# sensor.net
KiCad netlist of a schematic drawn in EAGLE
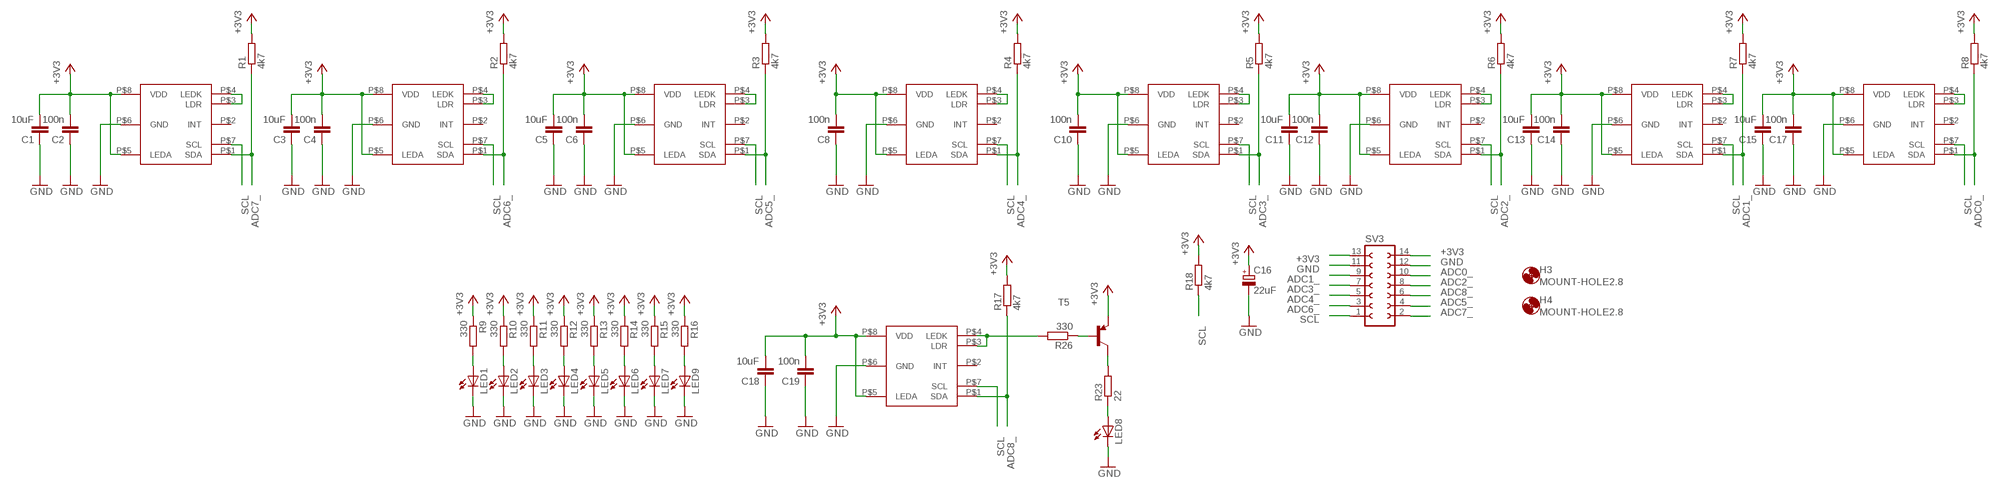
[diagram p0: schematic, sheet 1]

(export (version "E")
  (design (tool "Eeschema 10.0.6"))
  (components
    (comp (ref "C1")
      (value "10uF")
      (footprint "eagle-import:C0805")
      (libsource (lib "eagle-import") (part "C-EUC0805"))
    )
    (comp (ref "C2")
      (value "100n")
      (footprint "eagle-import:C0805")
      (libsource (lib "eagle-import") (part "C-EUC0805"))
    )
    (comp (ref "C3")
      (value "10uF")
      (footprint "eagle-import:C0805")
      (libsource (lib "eagle-import") (part "C-EUC0805"))
    )
    (comp (ref "C4")
      (value "100n")
      (footprint "eagle-import:C0805")
      (libsource (lib "eagle-import") (part "C-EUC0805"))
    )
    (comp (ref "C5")
      (value "10uF")
      (footprint "eagle-import:C0805")
      (libsource (lib "eagle-import") (part "C-EUC0805"))
    )
    (comp (ref "C6")
      (value "100n")
      (footprint "eagle-import:C0805")
      (libsource (lib "eagle-import") (part "C-EUC0805"))
    )
    (comp (ref "C8")
      (value "100n")
      (footprint "eagle-import:C0805")
      (libsource (lib "eagle-import") (part "C-EUC0805"))
    )
    (comp (ref "C10")
      (value "100n")
      (footprint "eagle-import:C0805")
      (libsource (lib "eagle-import") (part "C-EUC0805"))
    )
    (comp (ref "C11")
      (value "10uF")
      (footprint "eagle-import:C0805")
      (libsource (lib "eagle-import") (part "C-EUC0805"))
    )
    (comp (ref "C12")
      (value "100n")
      (footprint "eagle-import:C0805")
      (libsource (lib "eagle-import") (part "C-EUC0805"))
    )
    (comp (ref "C13")
      (value "10uF")
      (footprint "eagle-import:C0805")
      (libsource (lib "eagle-import") (part "C-EUC0805"))
    )
    (comp (ref "C14")
      (value "100n")
      (footprint "eagle-import:C0805")
      (libsource (lib "eagle-import") (part "C-EUC0805"))
    )
    (comp (ref "C15")
      (value "10uF")
      (footprint "eagle-import:C0805")
      (libsource (lib "eagle-import") (part "C-EUC0805"))
    )
    (comp (ref "C16")
      (value "22uF")
      (footprint "eagle-import:153CLV-0505")
      (libsource (lib "eagle-import") (part "CPOL-EU153CLV-0505"))
    )
    (comp (ref "C17")
      (value "100n")
      (footprint "eagle-import:C0805")
      (libsource (lib "eagle-import") (part "C-EUC0805"))
    )
    (comp (ref "C18")
      (value "10uF")
      (footprint "eagle-import:C0805")
      (libsource (lib "eagle-import") (part "C-EUC0805"))
    )
    (comp (ref "C19")
      (value "100n")
      (footprint "eagle-import:C0805")
      (libsource (lib "eagle-import") (part "C-EUC0805"))
    )
    (comp (ref "H3")
      (value "MOUNT-HOLE2.8")
      (footprint "eagle-import:2,8")
      (libsource (lib "eagle-import") (part "MOUNT-HOLE2.8"))
    )
    (comp (ref "H4")
      (value "MOUNT-HOLE2.8")
      (footprint "eagle-import:2,8")
      (libsource (lib "eagle-import") (part "MOUNT-HOLE2.8"))
    )
    (comp (ref "LED1")
      (value "LEDCHIPLED_1206")
      (footprint "eagle-import:CHIPLED_1206")
      (libsource (lib "eagle-import") (part "my_parts_LEDCHIPLED_1206"))
    )
    (comp (ref "LED2")
      (value "LEDCHIPLED_1206")
      (footprint "eagle-import:CHIPLED_1206")
      (libsource (lib "eagle-import") (part "my_parts_LEDCHIPLED_1206"))
    )
    (comp (ref "LED3")
      (value "LEDCHIPLED_1206")
      (footprint "eagle-import:CHIPLED_1206")
      (libsource (lib "eagle-import") (part "my_parts_LEDCHIPLED_1206"))
    )
    (comp (ref "LED4")
      (value "LEDCHIPLED_1206")
      (footprint "eagle-import:CHIPLED_1206")
      (libsource (lib "eagle-import") (part "my_parts_LEDCHIPLED_1206"))
    )
    (comp (ref "LED5")
      (value "LEDCHIPLED_1206")
      (footprint "eagle-import:CHIPLED_1206")
      (libsource (lib "eagle-import") (part "my_parts_LEDCHIPLED_1206"))
    )
    (comp (ref "LED6")
      (value "LEDCHIPLED_1206")
      (footprint "eagle-import:CHIPLED_1206")
      (libsource (lib "eagle-import") (part "my_parts_LEDCHIPLED_1206"))
    )
    (comp (ref "LED7")
      (value "LEDCHIPLED_1206")
      (footprint "eagle-import:CHIPLED_1206")
      (libsource (lib "eagle-import") (part "my_parts_LEDCHIPLED_1206"))
    )
    (comp (ref "LED8")
      (value "LED5MM")
      (footprint "eagle-import:LED5MM")
      (libsource (lib "eagle-import") (part "LED5MM"))
    )
    (comp (ref "LED9")
      (value "LEDCHIPLED_1206")
      (footprint "eagle-import:CHIPLED_1206")
      (libsource (lib "eagle-import") (part "my_parts_LEDCHIPLED_1206"))
    )
    (comp (ref "R1")
      (value "4k7")
      (footprint "eagle-import:M0805")
      (libsource (lib "eagle-import") (part "R-EU_M0805"))
    )
    (comp (ref "R2")
      (value "4k7")
      (footprint "eagle-import:M0805")
      (libsource (lib "eagle-import") (part "R-EU_M0805"))
    )
    (comp (ref "R3")
      (value "4k7")
      (footprint "eagle-import:M0805")
      (libsource (lib "eagle-import") (part "R-EU_M0805"))
    )
    (comp (ref "R4")
      (value "4k7")
      (footprint "eagle-import:M0805")
      (libsource (lib "eagle-import") (part "R-EU_M0805"))
    )
    (comp (ref "R5")
      (value "4k7")
      (footprint "eagle-import:M0805")
      (libsource (lib "eagle-import") (part "R-EU_M0805"))
    )
    (comp (ref "R6")
      (value "4k7")
      (footprint "eagle-import:M0805")
      (libsource (lib "eagle-import") (part "R-EU_M0805"))
    )
    (comp (ref "R7")
      (value "4k7")
      (footprint "eagle-import:M0805")
      (libsource (lib "eagle-import") (part "R-EU_M0805"))
    )
    (comp (ref "R8")
      (value "4k7")
      (footprint "eagle-import:M0805")
      (libsource (lib "eagle-import") (part "R-EU_M0805"))
    )
    (comp (ref "R9")
      (value "330")
      (footprint "eagle-import:M0805")
      (libsource (lib "eagle-import") (part "R-EU_M0805"))
    )
    (comp (ref "R10")
      (value "330")
      (footprint "eagle-import:M0805")
      (libsource (lib "eagle-import") (part "R-EU_M0805"))
    )
    (comp (ref "R11")
      (value "330")
      (footprint "eagle-import:M0805")
      (libsource (lib "eagle-import") (part "R-EU_M0805"))
    )
    (comp (ref "R12")
      (value "330")
      (footprint "eagle-import:M0805")
      (libsource (lib "eagle-import") (part "R-EU_M0805"))
    )
    (comp (ref "R13")
      (value "330")
      (footprint "eagle-import:M0805")
      (libsource (lib "eagle-import") (part "R-EU_M0805"))
    )
    (comp (ref "R14")
      (value "330")
      (footprint "eagle-import:M0805")
      (libsource (lib "eagle-import") (part "R-EU_M0805"))
    )
    (comp (ref "R15")
      (value "330")
      (footprint "eagle-import:M0805")
      (libsource (lib "eagle-import") (part "R-EU_M0805"))
    )
    (comp (ref "R16")
      (value "330")
      (footprint "eagle-import:M0805")
      (libsource (lib "eagle-import") (part "R-EU_M0805"))
    )
    (comp (ref "R17")
      (value "4k7")
      (footprint "eagle-import:M0805")
      (libsource (lib "eagle-import") (part "R-EU_M0805"))
    )
    (comp (ref "R18")
      (value "4k7")
      (footprint "eagle-import:M0805")
      (libsource (lib "eagle-import") (part "R-EU_M0805"))
    )
    (comp (ref "R23")
      (value "22")
      (footprint "eagle-import:M0805")
      (libsource (lib "eagle-import") (part "R-EU_M0805"))
    )
    (comp (ref "R26")
      (value "330")
      (footprint "eagle-import:M0805")
      (libsource (lib "eagle-import") (part "R-EU_M0805"))
    )
    (comp (ref "SV3")
      (value "FE07-2")
      (footprint "eagle-import:FE07-2")
      (libsource (lib "eagle-import") (part "FE07-2"))
    )
    (comp (ref "T5")
      (value "BC857A-PNP-SOT23-BEC")
      (footprint "eagle-import:SOT23-BEC")
      (libsource (lib "eagle-import") (part "-PNP-SOT23-BECBC857A"))
    )
    (comp (ref "U$1")
      (value "APDS9950")
      (footprint "eagle-import:APDS9950")
      (libsource (lib "eagle-import") (part "APDS9950"))
    )
    (comp (ref "U$2")
      (value "APDS9950_EDGE")
      (footprint "eagle-import:APDS9950_EDGE")
      (libsource (lib "eagle-import") (part "APDS9950_EDGE"))
    )
    (comp (ref "U$4")
      (value "APDS9950")
      (footprint "eagle-import:APDS9950")
      (libsource (lib "eagle-import") (part "APDS9950"))
    )
    (comp (ref "U$5")
      (value "APDS9950")
      (footprint "eagle-import:APDS9950")
      (libsource (lib "eagle-import") (part "APDS9950"))
    )
    (comp (ref "U$6")
      (value "APDS9950")
      (footprint "eagle-import:APDS9950")
      (libsource (lib "eagle-import") (part "APDS9950"))
    )
    (comp (ref "U$7")
      (value "APDS9950")
      (footprint "eagle-import:APDS9950")
      (libsource (lib "eagle-import") (part "APDS9950"))
    )
    (comp (ref "U$8")
      (value "APDS9950")
      (footprint "eagle-import:APDS9950")
      (libsource (lib "eagle-import") (part "APDS9950"))
    )
    (comp (ref "U$9")
      (value "APDS9950")
      (footprint "eagle-import:APDS9950")
      (libsource (lib "eagle-import") (part "APDS9950"))
    )
    (comp (ref "U$10")
      (value "APDS9950")
      (footprint "eagle-import:APDS9950")
      (libsource (lib "eagle-import") (part "APDS9950"))
    )
  )
  (nets
    (net (code "1") (name "+3V3") (class "Default")
      (node (ref "C1") (pin "2") (pinfunction "2_2") (pintype "passive"))
      (node (ref "C10") (pin "2") (pinfunction "2_2") (pintype "passive"))
      (node (ref "C11") (pin "2") (pinfunction "2_2") (pintype "passive"))
      (node (ref "C12") (pin "2") (pinfunction "2_2") (pintype "passive"))
      (node (ref "C13") (pin "2") (pinfunction "2_2") (pintype "passive"))
      (node (ref "C14") (pin "2") (pinfunction "2_2") (pintype "passive"))
      (node (ref "C15") (pin "2") (pinfunction "2_2") (pintype "passive"))
      (node (ref "C16") (pin "+") (pinfunction "+_+") (pintype "passive"))
      (node (ref "C17") (pin "2") (pinfunction "2_2") (pintype "passive"))
      (node (ref "C18") (pin "2") (pinfunction "2_2") (pintype "passive"))
      (node (ref "C19") (pin "2") (pinfunction "2_2") (pintype "passive"))
      (node (ref "C2") (pin "2") (pinfunction "2_2") (pintype "passive"))
      (node (ref "C3") (pin "2") (pinfunction "2_2") (pintype "passive"))
      (node (ref "C4") (pin "2") (pinfunction "2_2") (pintype "passive"))
      (node (ref "C5") (pin "2") (pinfunction "2_2") (pintype "passive"))
      (node (ref "C6") (pin "2") (pinfunction "2_2") (pintype "passive"))
      (node (ref "C8") (pin "2") (pinfunction "2_2") (pintype "passive"))
      (node (ref "R1") (pin "2") (pinfunction "2_2") (pintype "passive"))
      (node (ref "R10") (pin "1") (pinfunction "1_1") (pintype "passive"))
      (node (ref "R11") (pin "1") (pinfunction "1_1") (pintype "passive"))
      (node (ref "R12") (pin "1") (pinfunction "1_1") (pintype "passive"))
      (node (ref "R13") (pin "1") (pinfunction "1_1") (pintype "passive"))
      (node (ref "R14") (pin "1") (pinfunction "1_1") (pintype "passive"))
      (node (ref "R15") (pin "1") (pinfunction "1_1") (pintype "passive"))
      (node (ref "R16") (pin "1") (pinfunction "1_1") (pintype "passive"))
      (node (ref "R17") (pin "2") (pinfunction "2_2") (pintype "passive"))
      (node (ref "R18") (pin "2") (pinfunction "2_2") (pintype "passive"))
      (node (ref "R2") (pin "2") (pinfunction "2_2") (pintype "passive"))
      (node (ref "R3") (pin "2") (pinfunction "2_2") (pintype "passive"))
      (node (ref "R4") (pin "2") (pinfunction "2_2") (pintype "passive"))
      (node (ref "R5") (pin "2") (pinfunction "2_2") (pintype "passive"))
      (node (ref "R6") (pin "2") (pinfunction "2_2") (pintype "passive"))
      (node (ref "R7") (pin "2") (pinfunction "2_2") (pintype "passive"))
      (node (ref "R8") (pin "2") (pinfunction "2_2") (pintype "passive"))
      (node (ref "R9") (pin "1") (pinfunction "1_1") (pintype "passive"))
      (node (ref "SV3") (pin "13") (pinfunction "13_13") (pintype "passive"))
      (node (ref "SV3") (pin "14") (pinfunction "14_14") (pintype "passive"))
      (node (ref "T5") (pin "E") (pinfunction "E_E") (pintype "passive"))
      (node (ref "U$1") (pin "P$5") (pinfunction "LEDA_P$5") (pintype "bidirectional"))
      (node (ref "U$1") (pin "P$8") (pinfunction "VDD_P$8") (pintype "bidirectional"))
      (node (ref "U$10") (pin "P$5") (pinfunction "LEDA_P$5") (pintype "bidirectional"))
      (node (ref "U$10") (pin "P$8") (pinfunction "VDD_P$8") (pintype "bidirectional"))
      (node (ref "U$2") (pin "P$5") (pinfunction "LEDA_P$5") (pintype "bidirectional"))
      (node (ref "U$2") (pin "P$8") (pinfunction "VDD_P$8") (pintype "bidirectional"))
      (node (ref "U$4") (pin "P$5") (pinfunction "LEDA_P$5") (pintype "bidirectional"))
      (node (ref "U$4") (pin "P$8") (pinfunction "VDD_P$8") (pintype "bidirectional"))
      (node (ref "U$5") (pin "P$5") (pinfunction "LEDA_P$5") (pintype "bidirectional"))
      (node (ref "U$5") (pin "P$8") (pinfunction "VDD_P$8") (pintype "bidirectional"))
      (node (ref "U$6") (pin "P$5") (pinfunction "LEDA_P$5") (pintype "bidirectional"))
      (node (ref "U$6") (pin "P$8") (pinfunction "VDD_P$8") (pintype "bidirectional"))
      (node (ref "U$7") (pin "P$5") (pinfunction "LEDA_P$5") (pintype "bidirectional"))
      (node (ref "U$7") (pin "P$8") (pinfunction "VDD_P$8") (pintype "bidirectional"))
      (node (ref "U$8") (pin "P$5") (pinfunction "LEDA_P$5") (pintype "bidirectional"))
      (node (ref "U$8") (pin "P$8") (pinfunction "VDD_P$8") (pintype "bidirectional"))
      (node (ref "U$9") (pin "P$5") (pinfunction "LEDA_P$5") (pintype "bidirectional"))
      (node (ref "U$9") (pin "P$8") (pinfunction "VDD_P$8") (pintype "bidirectional"))
    )
    (net (code "2") (name "/ADC0_") (class "Default")
      (node (ref "R8") (pin "1") (pinfunction "1_1") (pintype "passive"))
      (node (ref "SV3") (pin "10") (pinfunction "10_10") (pintype "passive"))
      (node (ref "U$10") (pin "P$1") (pinfunction "SDA_P$1") (pintype "bidirectional"))
    )
    (net (code "3") (name "/ADC1_") (class "Default")
      (node (ref "R7") (pin "1") (pinfunction "1_1") (pintype "passive"))
      (node (ref "SV3") (pin "9") (pinfunction "9_9") (pintype "passive"))
      (node (ref "U$9") (pin "P$1") (pinfunction "SDA_P$1") (pintype "bidirectional"))
    )
    (net (code "4") (name "/ADC2_") (class "Default")
      (node (ref "R6") (pin "1") (pinfunction "1_1") (pintype "passive"))
      (node (ref "SV3") (pin "8") (pinfunction "8_8") (pintype "passive"))
      (node (ref "U$8") (pin "P$1") (pinfunction "SDA_P$1") (pintype "bidirectional"))
    )
    (net (code "5") (name "/ADC3_") (class "Default")
      (node (ref "R5") (pin "1") (pinfunction "1_1") (pintype "passive"))
      (node (ref "SV3") (pin "7") (pinfunction "7_7") (pintype "passive"))
      (node (ref "U$7") (pin "P$1") (pinfunction "SDA_P$1") (pintype "bidirectional"))
    )
    (net (code "6") (name "/ADC4_") (class "Default")
      (node (ref "R4") (pin "1") (pinfunction "1_1") (pintype "passive"))
      (node (ref "SV3") (pin "5") (pinfunction "5_5") (pintype "passive"))
      (node (ref "U$6") (pin "P$1") (pinfunction "SDA_P$1") (pintype "bidirectional"))
    )
    (net (code "7") (name "/ADC5_") (class "Default")
      (node (ref "R3") (pin "1") (pinfunction "1_1") (pintype "passive"))
      (node (ref "SV3") (pin "4") (pinfunction "4_4") (pintype "passive"))
      (node (ref "U$5") (pin "P$1") (pinfunction "SDA_P$1") (pintype "bidirectional"))
    )
    (net (code "8") (name "/ADC6_") (class "Default")
      (node (ref "R2") (pin "1") (pinfunction "1_1") (pintype "passive"))
      (node (ref "SV3") (pin "3") (pinfunction "3_3") (pintype "passive"))
      (node (ref "U$4") (pin "P$1") (pinfunction "SDA_P$1") (pintype "bidirectional"))
    )
    (net (code "9") (name "/ADC7_") (class "Default")
      (node (ref "R1") (pin "1") (pinfunction "1_1") (pintype "passive"))
      (node (ref "SV3") (pin "2") (pinfunction "2_2") (pintype "passive"))
      (node (ref "U$1") (pin "P$1") (pinfunction "SDA_P$1") (pintype "bidirectional"))
    )
    (net (code "10") (name "/ADC8_") (class "Default")
      (node (ref "R17") (pin "1") (pinfunction "1_1") (pintype "passive"))
      (node (ref "SV3") (pin "6") (pinfunction "6_6") (pintype "passive"))
      (node (ref "U$2") (pin "P$1") (pinfunction "SDA_P$1") (pintype "bidirectional"))
    )
    (net (code "11") (name "/SCL") (class "Default")
      (node (ref "R18") (pin "1") (pinfunction "1_1") (pintype "passive"))
      (node (ref "SV3") (pin "1") (pinfunction "1_1") (pintype "passive"))
      (node (ref "U$1") (pin "P$7") (pinfunction "SCL_P$7") (pintype "bidirectional"))
      (node (ref "U$10") (pin "P$7") (pinfunction "SCL_P$7") (pintype "bidirectional"))
      (node (ref "U$2") (pin "P$7") (pinfunction "SCL_P$7") (pintype "bidirectional"))
      (node (ref "U$4") (pin "P$7") (pinfunction "SCL_P$7") (pintype "bidirectional"))
      (node (ref "U$5") (pin "P$7") (pinfunction "SCL_P$7") (pintype "bidirectional"))
      (node (ref "U$6") (pin "P$7") (pinfunction "SCL_P$7") (pintype "bidirectional"))
      (node (ref "U$7") (pin "P$7") (pinfunction "SCL_P$7") (pintype "bidirectional"))
      (node (ref "U$8") (pin "P$7") (pinfunction "SCL_P$7") (pintype "bidirectional"))
      (node (ref "U$9") (pin "P$7") (pinfunction "SCL_P$7") (pintype "bidirectional"))
    )
    (net (code "12") (name "GND") (class "Default")
      (node (ref "C1") (pin "1") (pinfunction "1_1") (pintype "passive"))
      (node (ref "C10") (pin "1") (pinfunction "1_1") (pintype "passive"))
      (node (ref "C11") (pin "1") (pinfunction "1_1") (pintype "passive"))
      (node (ref "C12") (pin "1") (pinfunction "1_1") (pintype "passive"))
      (node (ref "C13") (pin "1") (pinfunction "1_1") (pintype "passive"))
      (node (ref "C14") (pin "1") (pinfunction "1_1") (pintype "passive"))
      (node (ref "C15") (pin "1") (pinfunction "1_1") (pintype "passive"))
      (node (ref "C16") (pin "-") (pinfunction "-_-") (pintype "passive"))
      (node (ref "C17") (pin "1") (pinfunction "1_1") (pintype "passive"))
      (node (ref "C18") (pin "1") (pinfunction "1_1") (pintype "passive"))
      (node (ref "C19") (pin "1") (pinfunction "1_1") (pintype "passive"))
      (node (ref "C2") (pin "1") (pinfunction "1_1") (pintype "passive"))
      (node (ref "C3") (pin "1") (pinfunction "1_1") (pintype "passive"))
      (node (ref "C4") (pin "1") (pinfunction "1_1") (pintype "passive"))
      (node (ref "C5") (pin "1") (pinfunction "1_1") (pintype "passive"))
      (node (ref "C6") (pin "1") (pinfunction "1_1") (pintype "passive"))
      (node (ref "C8") (pin "1") (pinfunction "1_1") (pintype "passive"))
      (node (ref "LED1") (pin "C") (pinfunction "C_C") (pintype "passive"))
      (node (ref "LED2") (pin "C") (pinfunction "C_C") (pintype "passive"))
      (node (ref "LED3") (pin "C") (pinfunction "C_C") (pintype "passive"))
      (node (ref "LED4") (pin "C") (pinfunction "C_C") (pintype "passive"))
      (node (ref "LED5") (pin "C") (pinfunction "C_C") (pintype "passive"))
      (node (ref "LED6") (pin "C") (pinfunction "C_C") (pintype "passive"))
      (node (ref "LED7") (pin "C") (pinfunction "C_C") (pintype "passive"))
      (node (ref "LED8") (pin "K") (pinfunction "C_K") (pintype "passive"))
      (node (ref "LED9") (pin "C") (pinfunction "C_C") (pintype "passive"))
      (node (ref "SV3") (pin "11") (pinfunction "11_11") (pintype "passive"))
      (node (ref "SV3") (pin "12") (pinfunction "12_12") (pintype "passive"))
      (node (ref "U$1") (pin "P$6") (pinfunction "GND_P$6") (pintype "bidirectional"))
      (node (ref "U$10") (pin "P$6") (pinfunction "GND_P$6") (pintype "bidirectional"))
      (node (ref "U$2") (pin "P$6") (pinfunction "GND_P$6") (pintype "bidirectional"))
      (node (ref "U$4") (pin "P$6") (pinfunction "GND_P$6") (pintype "bidirectional"))
      (node (ref "U$5") (pin "P$6") (pinfunction "GND_P$6") (pintype "bidirectional"))
      (node (ref "U$6") (pin "P$6") (pinfunction "GND_P$6") (pintype "bidirectional"))
      (node (ref "U$7") (pin "P$6") (pinfunction "GND_P$6") (pintype "bidirectional"))
      (node (ref "U$8") (pin "P$6") (pinfunction "GND_P$6") (pintype "bidirectional"))
      (node (ref "U$9") (pin "P$6") (pinfunction "GND_P$6") (pintype "bidirectional"))
    )
    (net (code "13") (name "Net-(LED1-PadA)") (class "Default")
      (node (ref "LED1") (pin "A") (pinfunction "A_A") (pintype "passive"))
      (node (ref "R9") (pin "2") (pinfunction "2_2") (pintype "passive"))
    )
    (net (code "14") (name "Net-(LED2-PadA)") (class "Default")
      (node (ref "LED2") (pin "A") (pinfunction "A_A") (pintype "passive"))
      (node (ref "R10") (pin "2") (pinfunction "2_2") (pintype "passive"))
    )
    (net (code "15") (name "Net-(LED3-PadA)") (class "Default")
      (node (ref "LED3") (pin "A") (pinfunction "A_A") (pintype "passive"))
      (node (ref "R11") (pin "2") (pinfunction "2_2") (pintype "passive"))
    )
    (net (code "16") (name "Net-(LED4-PadA)") (class "Default")
      (node (ref "LED4") (pin "A") (pinfunction "A_A") (pintype "passive"))
      (node (ref "R12") (pin "2") (pinfunction "2_2") (pintype "passive"))
    )
    (net (code "17") (name "Net-(LED5-PadA)") (class "Default")
      (node (ref "LED5") (pin "A") (pinfunction "A_A") (pintype "passive"))
      (node (ref "R13") (pin "2") (pinfunction "2_2") (pintype "passive"))
    )
    (net (code "18") (name "Net-(LED6-PadA)") (class "Default")
      (node (ref "LED6") (pin "A") (pinfunction "A_A") (pintype "passive"))
      (node (ref "R14") (pin "2") (pinfunction "2_2") (pintype "passive"))
    )
    (net (code "19") (name "Net-(LED7-PadA)") (class "Default")
      (node (ref "LED7") (pin "A") (pinfunction "A_A") (pintype "passive"))
      (node (ref "R15") (pin "2") (pinfunction "2_2") (pintype "passive"))
    )
    (net (code "20") (name "Net-(LED8-PadA)") (class "Default")
      (node (ref "LED8") (pin "A") (pinfunction "A_A") (pintype "passive"))
      (node (ref "R23") (pin "1") (pinfunction "1_1") (pintype "passive"))
    )
    (net (code "21") (name "Net-(LED9-PadA)") (class "Default")
      (node (ref "LED9") (pin "A") (pinfunction "A_A") (pintype "passive"))
      (node (ref "R16") (pin "2") (pinfunction "2_2") (pintype "passive"))
    )
    (net (code "22") (name "Net-(R23-Pad2)") (class "Default")
      (node (ref "R23") (pin "2") (pinfunction "2_2") (pintype "passive"))
      (node (ref "T5") (pin "C") (pinfunction "C_C") (pintype "passive"))
    )
    (net (code "23") (name "Net-(R26-Pad1)") (class "Default")
      (node (ref "R26") (pin "1") (pinfunction "1_1") (pintype "passive"))
      (node (ref "T5") (pin "B") (pinfunction "B_B") (pintype "passive"))
    )
    (net (code "24") (name "Net-(U$1-LDR)") (class "Default")
      (node (ref "U$1") (pin "P$3") (pinfunction "LDR_P$3") (pintype "bidirectional"))
      (node (ref "U$1") (pin "P$4") (pinfunction "LEDK_P$4") (pintype "bidirectional"))
    )
    (net (code "25") (name "Net-(U$2-LDR)") (class "Default")
      (node (ref "R26") (pin "2") (pinfunction "2_2") (pintype "passive"))
      (node (ref "U$2") (pin "P$3") (pinfunction "LDR_P$3") (pintype "bidirectional"))
      (node (ref "U$2") (pin "P$4") (pinfunction "LEDK_P$4") (pintype "bidirectional"))
    )
    (net (code "26") (name "Net-(U$4-LDR)") (class "Default")
      (node (ref "U$4") (pin "P$3") (pinfunction "LDR_P$3") (pintype "bidirectional"))
      (node (ref "U$4") (pin "P$4") (pinfunction "LEDK_P$4") (pintype "bidirectional"))
    )
    (net (code "27") (name "Net-(U$5-LDR)") (class "Default")
      (node (ref "U$5") (pin "P$3") (pinfunction "LDR_P$3") (pintype "bidirectional"))
      (node (ref "U$5") (pin "P$4") (pinfunction "LEDK_P$4") (pintype "bidirectional"))
    )
    (net (code "28") (name "Net-(U$6-LDR)") (class "Default")
      (node (ref "U$6") (pin "P$3") (pinfunction "LDR_P$3") (pintype "bidirectional"))
      (node (ref "U$6") (pin "P$4") (pinfunction "LEDK_P$4") (pintype "bidirectional"))
    )
    (net (code "29") (name "Net-(U$7-LDR)") (class "Default")
      (node (ref "U$7") (pin "P$3") (pinfunction "LDR_P$3") (pintype "bidirectional"))
      (node (ref "U$7") (pin "P$4") (pinfunction "LEDK_P$4") (pintype "bidirectional"))
    )
    (net (code "30") (name "Net-(U$8-LDR)") (class "Default")
      (node (ref "U$8") (pin "P$3") (pinfunction "LDR_P$3") (pintype "bidirectional"))
      (node (ref "U$8") (pin "P$4") (pinfunction "LEDK_P$4") (pintype "bidirectional"))
    )
    (net (code "31") (name "Net-(U$9-LDR)") (class "Default")
      (node (ref "U$9") (pin "P$3") (pinfunction "LDR_P$3") (pintype "bidirectional"))
      (node (ref "U$9") (pin "P$4") (pinfunction "LEDK_P$4") (pintype "bidirectional"))
    )
    (net (code "32") (name "Net-(U$10-LDR)") (class "Default")
      (node (ref "U$10") (pin "P$3") (pinfunction "LDR_P$3") (pintype "bidirectional"))
      (node (ref "U$10") (pin "P$4") (pinfunction "LEDK_P$4") (pintype "bidirectional"))
    )
    (net (code "33") (name "unconnected-(U$1-INT-PadP$2)") (class "Default")
      (node (ref "U$1") (pin "P$2") (pinfunction "INT_P$2") (pintype "bidirectional"))
    )
    (net (code "34") (name "unconnected-(U$2-INT-PadP$2)") (class "Default")
      (node (ref "U$2") (pin "P$2") (pinfunction "INT_P$2") (pintype "bidirectional"))
    )
    (net (code "35") (name "unconnected-(U$4-INT-PadP$2)") (class "Default")
      (node (ref "U$4") (pin "P$2") (pinfunction "INT_P$2") (pintype "bidirectional"))
    )
    (net (code "36") (name "unconnected-(U$5-INT-PadP$2)") (class "Default")
      (node (ref "U$5") (pin "P$2") (pinfunction "INT_P$2") (pintype "bidirectional"))
    )
    (net (code "37") (name "unconnected-(U$6-INT-PadP$2)") (class "Default")
      (node (ref "U$6") (pin "P$2") (pinfunction "INT_P$2") (pintype "bidirectional"))
    )
    (net (code "38") (name "unconnected-(U$7-INT-PadP$2)") (class "Default")
      (node (ref "U$7") (pin "P$2") (pinfunction "INT_P$2") (pintype "bidirectional"))
    )
    (net (code "39") (name "unconnected-(U$8-INT-PadP$2)") (class "Default")
      (node (ref "U$8") (pin "P$2") (pinfunction "INT_P$2") (pintype "bidirectional"))
    )
    (net (code "40") (name "unconnected-(U$9-INT-PadP$2)") (class "Default")
      (node (ref "U$9") (pin "P$2") (pinfunction "INT_P$2") (pintype "bidirectional"))
    )
    (net (code "41") (name "unconnected-(U$10-INT-PadP$2)") (class "Default")
      (node (ref "U$10") (pin "P$2") (pinfunction "INT_P$2") (pintype "bidirectional"))
    )
  )
)
